# R212X.net
KiCad netlist of a schematic drawn in EAGLE
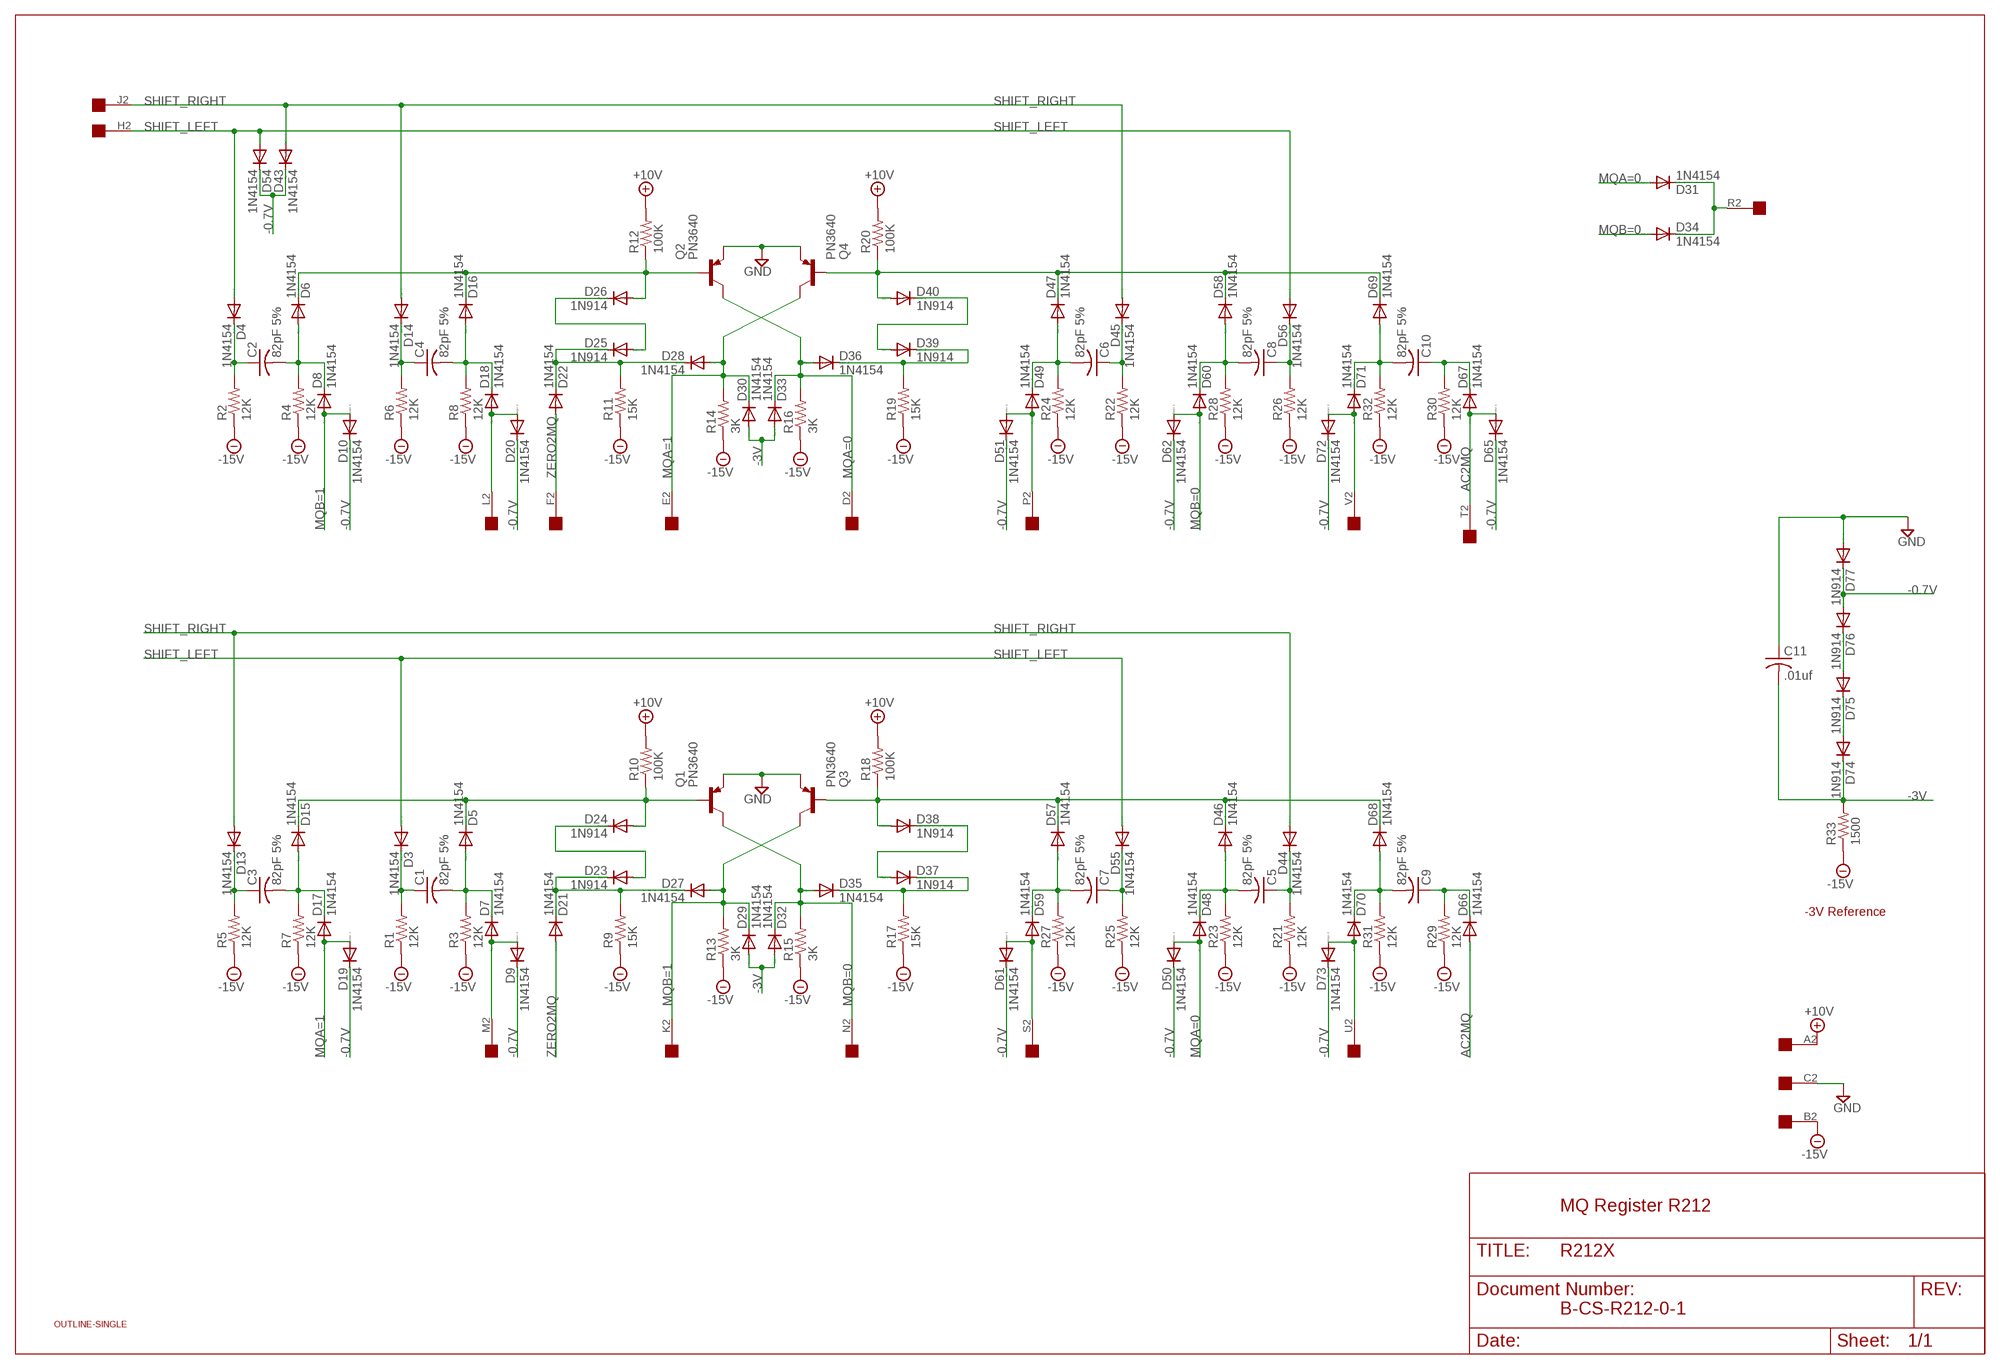
[diagram p0: schematic, sheet 1]

(export (version "E")
  (design (tool "Eeschema 10.0.6"))
  (components
    (comp (ref "C1")
      (value "82pF 5%")
      (footprint "eagle-import:C050-025X075")
      (libsource (lib "eagle-import") (part "C-US050-025X075"))
    )
    (comp (ref "C2")
      (value "82pF 5%")
      (footprint "eagle-import:C050-025X075")
      (libsource (lib "eagle-import") (part "C-US050-025X075"))
    )
    (comp (ref "C3")
      (value "82pF 5%")
      (footprint "eagle-import:C050-025X075")
      (libsource (lib "eagle-import") (part "C-US050-025X075"))
    )
    (comp (ref "C4")
      (value "82pF 5%")
      (footprint "eagle-import:C050-025X075")
      (libsource (lib "eagle-import") (part "C-US050-025X075"))
    )
    (comp (ref "C5")
      (value "82pF 5%")
      (footprint "eagle-import:C050-025X075")
      (libsource (lib "eagle-import") (part "C-US050-025X075"))
    )
    (comp (ref "C6")
      (value "82pF 5%")
      (footprint "eagle-import:C050-025X075")
      (libsource (lib "eagle-import") (part "C-US050-025X075"))
    )
    (comp (ref "C7")
      (value "82pF 5%")
      (footprint "eagle-import:C050-025X075")
      (libsource (lib "eagle-import") (part "C-US050-025X075"))
    )
    (comp (ref "C8")
      (value "82pF 5%")
      (footprint "eagle-import:C050-025X075")
      (libsource (lib "eagle-import") (part "C-US050-025X075"))
    )
    (comp (ref "C9")
      (value "82pF 5%")
      (footprint "eagle-import:C050-025X075")
      (libsource (lib "eagle-import") (part "C-US050-025X075"))
    )
    (comp (ref "C10")
      (value "82pF 5%")
      (footprint "eagle-import:C050-025X075")
      (libsource (lib "eagle-import") (part "C-US050-025X075"))
    )
    (comp (ref "C11")
      (value ".01uf")
      (footprint "eagle-import:C050-025X075")
      (libsource (lib "eagle-import") (part "C-US050-025X075"))
    )
    (comp (ref "D3")
      (value "1N4154")
      (footprint "eagle-import:DO35-10")
      (libsource (lib "eagle-import") (part "1N4148DO35-10"))
    )
    (comp (ref "D4")
      (value "1N4154")
      (footprint "eagle-import:DO35-10")
      (libsource (lib "eagle-import") (part "1N4148DO35-10"))
    )
    (comp (ref "D5")
      (value "1N4154")
      (footprint "eagle-import:DO35-10")
      (libsource (lib "eagle-import") (part "1N4148DO35-10"))
    )
    (comp (ref "D6")
      (value "1N4154")
      (footprint "eagle-import:DO35-10")
      (libsource (lib "eagle-import") (part "1N4148DO35-10"))
    )
    (comp (ref "D7")
      (value "1N4154")
      (footprint "eagle-import:DO35-10")
      (libsource (lib "eagle-import") (part "1N4148DO35-10"))
    )
    (comp (ref "D8")
      (value "1N4154")
      (footprint "eagle-import:DO35-10")
      (libsource (lib "eagle-import") (part "1N4148DO35-10"))
    )
    (comp (ref "D9")
      (value "1N4154")
      (footprint "eagle-import:DO35-10")
      (libsource (lib "eagle-import") (part "1N4148DO35-10"))
    )
    (comp (ref "D10")
      (value "1N4154")
      (footprint "eagle-import:DO35-10")
      (libsource (lib "eagle-import") (part "1N4148DO35-10"))
    )
    (comp (ref "D13")
      (value "1N4154")
      (footprint "eagle-import:DO35-10")
      (libsource (lib "eagle-import") (part "1N4148DO35-10"))
    )
    (comp (ref "D14")
      (value "1N4154")
      (footprint "eagle-import:DO35-10")
      (libsource (lib "eagle-import") (part "1N4148DO35-10"))
    )
    (comp (ref "D15")
      (value "1N4154")
      (footprint "eagle-import:DO35-10")
      (libsource (lib "eagle-import") (part "1N4148DO35-10"))
    )
    (comp (ref "D16")
      (value "1N4154")
      (footprint "eagle-import:DO35-10")
      (libsource (lib "eagle-import") (part "1N4148DO35-10"))
    )
    (comp (ref "D17")
      (value "1N4154")
      (footprint "eagle-import:DO35-10")
      (libsource (lib "eagle-import") (part "1N4148DO35-10"))
    )
    (comp (ref "D18")
      (value "1N4154")
      (footprint "eagle-import:DO35-10")
      (libsource (lib "eagle-import") (part "1N4148DO35-10"))
    )
    (comp (ref "D19")
      (value "1N4154")
      (footprint "eagle-import:DO35-10")
      (libsource (lib "eagle-import") (part "1N4148DO35-10"))
    )
    (comp (ref "D20")
      (value "1N4154")
      (footprint "eagle-import:DO35-10")
      (libsource (lib "eagle-import") (part "1N4148DO35-10"))
    )
    (comp (ref "D21")
      (value "1N4154")
      (footprint "eagle-import:DO35-10")
      (libsource (lib "eagle-import") (part "1N4148DO35-10"))
    )
    (comp (ref "D22")
      (value "1N4154")
      (footprint "eagle-import:DO35-10")
      (libsource (lib "eagle-import") (part "1N4148DO35-10"))
    )
    (comp (ref "D23")
      (value "1N914")
      (footprint "eagle-import:DO35-10")
      (libsource (lib "eagle-import") (part "1N4148DO35-10"))
    )
    (comp (ref "D24")
      (value "1N914")
      (footprint "eagle-import:DO35-10")
      (libsource (lib "eagle-import") (part "1N4148DO35-10"))
    )
    (comp (ref "D25")
      (value "1N914")
      (footprint "eagle-import:DO35-10")
      (libsource (lib "eagle-import") (part "1N4148DO35-10"))
    )
    (comp (ref "D26")
      (value "1N914")
      (footprint "eagle-import:DO35-10")
      (libsource (lib "eagle-import") (part "1N4148DO35-10"))
    )
    (comp (ref "D27")
      (value "1N4154")
      (footprint "eagle-import:DO35-10")
      (libsource (lib "eagle-import") (part "1N4148DO35-10"))
    )
    (comp (ref "D28")
      (value "1N4154")
      (footprint "eagle-import:DO35-10")
      (libsource (lib "eagle-import") (part "1N4148DO35-10"))
    )
    (comp (ref "D29")
      (value "1N4154")
      (footprint "eagle-import:DO35-10")
      (libsource (lib "eagle-import") (part "1N4148DO35-10"))
    )
    (comp (ref "D30")
      (value "1N4154")
      (footprint "eagle-import:DO35-10")
      (libsource (lib "eagle-import") (part "1N4148DO35-10"))
    )
    (comp (ref "D31")
      (value "1N4154")
      (footprint "eagle-import:DO35-10")
      (libsource (lib "eagle-import") (part "1N4148DO35-10"))
    )
    (comp (ref "D32")
      (value "1N4154")
      (footprint "eagle-import:DO35-10")
      (libsource (lib "eagle-import") (part "1N4148DO35-10"))
    )
    (comp (ref "D33")
      (value "1N4154")
      (footprint "eagle-import:DO35-10")
      (libsource (lib "eagle-import") (part "1N4148DO35-10"))
    )
    (comp (ref "D34")
      (value "1N4154")
      (footprint "eagle-import:DO35-10")
      (libsource (lib "eagle-import") (part "1N4148DO35-10"))
    )
    (comp (ref "D35")
      (value "1N4154")
      (footprint "eagle-import:DO35-10")
      (libsource (lib "eagle-import") (part "1N4148DO35-10"))
    )
    (comp (ref "D36")
      (value "1N4154")
      (footprint "eagle-import:DO35-10")
      (libsource (lib "eagle-import") (part "1N4148DO35-10"))
    )
    (comp (ref "D37")
      (value "1N914")
      (footprint "eagle-import:DO35-10")
      (libsource (lib "eagle-import") (part "1N4148DO35-10"))
    )
    (comp (ref "D38")
      (value "1N914")
      (footprint "eagle-import:DO35-10")
      (libsource (lib "eagle-import") (part "1N4148DO35-10"))
    )
    (comp (ref "D39")
      (value "1N914")
      (footprint "eagle-import:DO35-10")
      (libsource (lib "eagle-import") (part "1N4148DO35-10"))
    )
    (comp (ref "D40")
      (value "1N914")
      (footprint "eagle-import:DO35-10")
      (libsource (lib "eagle-import") (part "1N4148DO35-10"))
    )
    (comp (ref "D43")
      (value "1N4154")
      (footprint "eagle-import:DO35-10")
      (libsource (lib "eagle-import") (part "1N4148DO35-10"))
    )
    (comp (ref "D44")
      (value "1N4154")
      (footprint "eagle-import:DO35-10")
      (libsource (lib "eagle-import") (part "1N4148DO35-10"))
    )
    (comp (ref "D45")
      (value "1N4154")
      (footprint "eagle-import:DO35-10")
      (libsource (lib "eagle-import") (part "1N4148DO35-10"))
    )
    (comp (ref "D46")
      (value "1N4154")
      (footprint "eagle-import:DO35-10")
      (libsource (lib "eagle-import") (part "1N4148DO35-10"))
    )
    (comp (ref "D47")
      (value "1N4154")
      (footprint "eagle-import:DO35-10")
      (libsource (lib "eagle-import") (part "1N4148DO35-10"))
    )
    (comp (ref "D48")
      (value "1N4154")
      (footprint "eagle-import:DO35-10")
      (libsource (lib "eagle-import") (part "1N4148DO35-10"))
    )
    (comp (ref "D49")
      (value "1N4154")
      (footprint "eagle-import:DO35-10")
      (libsource (lib "eagle-import") (part "1N4148DO35-10"))
    )
    (comp (ref "D50")
      (value "1N4154")
      (footprint "eagle-import:DO35-10")
      (libsource (lib "eagle-import") (part "1N4148DO35-10"))
    )
    (comp (ref "D51")
      (value "1N4154")
      (footprint "eagle-import:DO35-10")
      (libsource (lib "eagle-import") (part "1N4148DO35-10"))
    )
    (comp (ref "D54")
      (value "1N4154")
      (footprint "eagle-import:DO35-10")
      (libsource (lib "eagle-import") (part "1N4148DO35-10"))
    )
    (comp (ref "D55")
      (value "1N4154")
      (footprint "eagle-import:DO35-10")
      (libsource (lib "eagle-import") (part "1N4148DO35-10"))
    )
    (comp (ref "D56")
      (value "1N4154")
      (footprint "eagle-import:DO35-10")
      (libsource (lib "eagle-import") (part "1N4148DO35-10"))
    )
    (comp (ref "D57")
      (value "1N4154")
      (footprint "eagle-import:DO35-10")
      (libsource (lib "eagle-import") (part "1N4148DO35-10"))
    )
    (comp (ref "D58")
      (value "1N4154")
      (footprint "eagle-import:DO35-10")
      (libsource (lib "eagle-import") (part "1N4148DO35-10"))
    )
    (comp (ref "D59")
      (value "1N4154")
      (footprint "eagle-import:DO35-10")
      (libsource (lib "eagle-import") (part "1N4148DO35-10"))
    )
    (comp (ref "D60")
      (value "1N4154")
      (footprint "eagle-import:DO35-10")
      (libsource (lib "eagle-import") (part "1N4148DO35-10"))
    )
    (comp (ref "D61")
      (value "1N4154")
      (footprint "eagle-import:DO35-10")
      (libsource (lib "eagle-import") (part "1N4148DO35-10"))
    )
    (comp (ref "D62")
      (value "1N4154")
      (footprint "eagle-import:DO35-10")
      (libsource (lib "eagle-import") (part "1N4148DO35-10"))
    )
    (comp (ref "D65")
      (value "1N4154")
      (footprint "eagle-import:DO35-10")
      (libsource (lib "eagle-import") (part "1N4148DO35-10"))
    )
    (comp (ref "D66")
      (value "1N4154")
      (footprint "eagle-import:DO35-10")
      (libsource (lib "eagle-import") (part "1N4148DO35-10"))
    )
    (comp (ref "D67")
      (value "1N4154")
      (footprint "eagle-import:DO35-10")
      (libsource (lib "eagle-import") (part "1N4148DO35-10"))
    )
    (comp (ref "D68")
      (value "1N4154")
      (footprint "eagle-import:DO35-10")
      (libsource (lib "eagle-import") (part "1N4148DO35-10"))
    )
    (comp (ref "D69")
      (value "1N4154")
      (footprint "eagle-import:DO35-10")
      (libsource (lib "eagle-import") (part "1N4148DO35-10"))
    )
    (comp (ref "D70")
      (value "1N4154")
      (footprint "eagle-import:DO35-10")
      (libsource (lib "eagle-import") (part "1N4148DO35-10"))
    )
    (comp (ref "D71")
      (value "1N4154")
      (footprint "eagle-import:DO35-10")
      (libsource (lib "eagle-import") (part "1N4148DO35-10"))
    )
    (comp (ref "D72")
      (value "1N4154")
      (footprint "eagle-import:DO35-10")
      (libsource (lib "eagle-import") (part "1N4148DO35-10"))
    )
    (comp (ref "D73")
      (value "1N4154")
      (footprint "eagle-import:DO35-10")
      (libsource (lib "eagle-import") (part "1N4148DO35-10"))
    )
    (comp (ref "D74")
      (value "1N914")
      (footprint "eagle-import:DO35-10")
      (libsource (lib "eagle-import") (part "1N4148DO35-10"))
    )
    (comp (ref "D75")
      (value "1N914")
      (footprint "eagle-import:DO35-10")
      (libsource (lib "eagle-import") (part "1N4148DO35-10"))
    )
    (comp (ref "D76")
      (value "1N914")
      (footprint "eagle-import:DO35-10")
      (libsource (lib "eagle-import") (part "1N4148DO35-10"))
    )
    (comp (ref "D77")
      (value "1N914")
      (footprint "eagle-import:DO35-10")
      (libsource (lib "eagle-import") (part "1N4148DO35-10"))
    )
    (comp (ref "Q1")
      (value "PN3640")
      (footprint "eagle-import:TO39")
      (libsource (lib "eagle-import") (part "2N3637"))
    )
    (comp (ref "Q2")
      (value "PN3640")
      (footprint "eagle-import:TO39")
      (libsource (lib "eagle-import") (part "2N3637"))
    )
    (comp (ref "Q3")
      (value "PN3640")
      (footprint "eagle-import:TO39")
      (libsource (lib "eagle-import") (part "2N3637"))
    )
    (comp (ref "Q4")
      (value "PN3640")
      (footprint "eagle-import:TO39")
      (libsource (lib "eagle-import") (part "2N3637"))
    )
    (comp (ref "R1")
      (value "12K")
      (footprint "eagle-import:0207_10")
      (libsource (lib "eagle-import") (part "R-US_0207/10"))
    )
    (comp (ref "R2")
      (value "12K")
      (footprint "eagle-import:0207_10")
      (libsource (lib "eagle-import") (part "R-US_0207/10"))
    )
    (comp (ref "R3")
      (value "12K")
      (footprint "eagle-import:0207_10")
      (libsource (lib "eagle-import") (part "R-US_0207/10"))
    )
    (comp (ref "R4")
      (value "12K")
      (footprint "eagle-import:0207_10")
      (libsource (lib "eagle-import") (part "R-US_0207/10"))
    )
    (comp (ref "R5")
      (value "12K")
      (footprint "eagle-import:0207_10")
      (libsource (lib "eagle-import") (part "R-US_0207/10"))
    )
    (comp (ref "R6")
      (value "12K")
      (footprint "eagle-import:0207_10")
      (libsource (lib "eagle-import") (part "R-US_0207/10"))
    )
    (comp (ref "R7")
      (value "12K")
      (footprint "eagle-import:0207_10")
      (libsource (lib "eagle-import") (part "R-US_0207/10"))
    )
    (comp (ref "R8")
      (value "12K")
      (footprint "eagle-import:0207_10")
      (libsource (lib "eagle-import") (part "R-US_0207/10"))
    )
    (comp (ref "R9")
      (value "15K")
      (footprint "eagle-import:0207_10")
      (libsource (lib "eagle-import") (part "R-US_0207/10"))
    )
    (comp (ref "R10")
      (value "100K")
      (footprint "eagle-import:0207_10")
      (libsource (lib "eagle-import") (part "R-US_0207/10"))
    )
    (comp (ref "R11")
      (value "15K")
      (footprint "eagle-import:0207_10")
      (libsource (lib "eagle-import") (part "R-US_0207/10"))
    )
    (comp (ref "R12")
      (value "100K")
      (footprint "eagle-import:0207_10")
      (libsource (lib "eagle-import") (part "R-US_0207/10"))
    )
    (comp (ref "R13")
      (value "3K")
      (footprint "eagle-import:0207_10")
      (libsource (lib "eagle-import") (part "R-US_0207/10"))
    )
    (comp (ref "R14")
      (value "3K")
      (footprint "eagle-import:0207_10")
      (libsource (lib "eagle-import") (part "R-US_0207/10"))
    )
    (comp (ref "R15")
      (value "3K")
      (footprint "eagle-import:0207_10")
      (libsource (lib "eagle-import") (part "R-US_0207/10"))
    )
    (comp (ref "R16")
      (value "3K")
      (footprint "eagle-import:0207_10")
      (libsource (lib "eagle-import") (part "R-US_0207/10"))
    )
    (comp (ref "R17")
      (value "15K")
      (footprint "eagle-import:0207_10")
      (libsource (lib "eagle-import") (part "R-US_0207/10"))
    )
    (comp (ref "R18")
      (value "100K")
      (footprint "eagle-import:0207_10")
      (libsource (lib "eagle-import") (part "R-US_0207/10"))
    )
    (comp (ref "R19")
      (value "15K")
      (footprint "eagle-import:0207_10")
      (libsource (lib "eagle-import") (part "R-US_0207/10"))
    )
    (comp (ref "R20")
      (value "100K")
      (footprint "eagle-import:0207_10")
      (libsource (lib "eagle-import") (part "R-US_0207/10"))
    )
    (comp (ref "R21")
      (value "12K")
      (footprint "eagle-import:0207_10")
      (libsource (lib "eagle-import") (part "R-US_0207/10"))
    )
    (comp (ref "R22")
      (value "12K")
      (footprint "eagle-import:0207_10")
      (libsource (lib "eagle-import") (part "R-US_0207/10"))
    )
    (comp (ref "R23")
      (value "12K")
      (footprint "eagle-import:0207_10")
      (libsource (lib "eagle-import") (part "R-US_0207/10"))
    )
    (comp (ref "R24")
      (value "12K")
      (footprint "eagle-import:0207_10")
      (libsource (lib "eagle-import") (part "R-US_0207/10"))
    )
    (comp (ref "R25")
      (value "12K")
      (footprint "eagle-import:0207_10")
      (libsource (lib "eagle-import") (part "R-US_0207/10"))
    )
    (comp (ref "R26")
      (value "12K")
      (footprint "eagle-import:0207_10")
      (libsource (lib "eagle-import") (part "R-US_0207/10"))
    )
    (comp (ref "R27")
      (value "12K")
      (footprint "eagle-import:0207_10")
      (libsource (lib "eagle-import") (part "R-US_0207/10"))
    )
    (comp (ref "R28")
      (value "12K")
      (footprint "eagle-import:0207_10")
      (libsource (lib "eagle-import") (part "R-US_0207/10"))
    )
    (comp (ref "R29")
      (value "12K")
      (footprint "eagle-import:0207_10")
      (libsource (lib "eagle-import") (part "R-US_0207/10"))
    )
    (comp (ref "R30")
      (value "12K")
      (footprint "eagle-import:0207_10")
      (libsource (lib "eagle-import") (part "R-US_0207/10"))
    )
    (comp (ref "R31")
      (value "12K")
      (footprint "eagle-import:0207_10")
      (libsource (lib "eagle-import") (part "R-US_0207/10"))
    )
    (comp (ref "R32")
      (value "12K")
      (footprint "eagle-import:0207_10")
      (libsource (lib "eagle-import") (part "R-US_0207/10"))
    )
    (comp (ref "R33")
      (value "1500")
      (footprint "eagle-import:0207_10")
      (libsource (lib "eagle-import") (part "R-US_0207/10"))
    )
    (comp (ref "U$1")
      (value "OUTLINE-SINGLE")
      (footprint "eagle-import:SINGLE")
      (libsource (lib "eagle-import") (part "OUTLINE-SINGLE"))
    )
    (comp (ref "U$2")
      (value "EDGE-1")
      (footprint "eagle-import:EDGE-CON1")
      (libsource (lib "eagle-import") (part "EDGE-1"))
    )
  )
  (nets
    (net (code "1") (name "+10V") (class "Default")
      (node (ref "R10") (pin "2") (pinfunction "2_2") (pintype "passive"))
      (node (ref "R12") (pin "2") (pinfunction "2_2") (pintype "passive"))
      (node (ref "R18") (pin "2") (pinfunction "2_2") (pintype "passive"))
      (node (ref "R20") (pin "2") (pinfunction "2_2") (pintype "passive"))
      (node (ref "U$2") (pin "A2") (pinfunction "1_A2") (pintype "bidirectional"))
    )
    (net (code "2") (name "-15V") (class "Default")
      (node (ref "R1") (pin "1") (pinfunction "1_1") (pintype "passive"))
      (node (ref "R11") (pin "1") (pinfunction "1_1") (pintype "passive"))
      (node (ref "R13") (pin "1") (pinfunction "1_1") (pintype "passive"))
      (node (ref "R14") (pin "1") (pinfunction "1_1") (pintype "passive"))
      (node (ref "R15") (pin "1") (pinfunction "1_1") (pintype "passive"))
      (node (ref "R16") (pin "1") (pinfunction "1_1") (pintype "passive"))
      (node (ref "R17") (pin "1") (pinfunction "1_1") (pintype "passive"))
      (node (ref "R19") (pin "1") (pinfunction "1_1") (pintype "passive"))
      (node (ref "R2") (pin "1") (pinfunction "1_1") (pintype "passive"))
      (node (ref "R21") (pin "1") (pinfunction "1_1") (pintype "passive"))
      (node (ref "R22") (pin "1") (pinfunction "1_1") (pintype "passive"))
      (node (ref "R23") (pin "1") (pinfunction "1_1") (pintype "passive"))
      (node (ref "R24") (pin "1") (pinfunction "1_1") (pintype "passive"))
      (node (ref "R25") (pin "1") (pinfunction "1_1") (pintype "passive"))
      (node (ref "R26") (pin "1") (pinfunction "1_1") (pintype "passive"))
      (node (ref "R27") (pin "1") (pinfunction "1_1") (pintype "passive"))
      (node (ref "R28") (pin "1") (pinfunction "1_1") (pintype "passive"))
      (node (ref "R29") (pin "1") (pinfunction "1_1") (pintype "passive"))
      (node (ref "R3") (pin "1") (pinfunction "1_1") (pintype "passive"))
      (node (ref "R30") (pin "1") (pinfunction "1_1") (pintype "passive"))
      (node (ref "R31") (pin "1") (pinfunction "1_1") (pintype "passive"))
      (node (ref "R32") (pin "1") (pinfunction "1_1") (pintype "passive"))
      (node (ref "R33") (pin "1") (pinfunction "1_1") (pintype "passive"))
      (node (ref "R4") (pin "1") (pinfunction "1_1") (pintype "passive"))
      (node (ref "R5") (pin "1") (pinfunction "1_1") (pintype "passive"))
      (node (ref "R6") (pin "1") (pinfunction "1_1") (pintype "passive"))
      (node (ref "R7") (pin "1") (pinfunction "1_1") (pintype "passive"))
      (node (ref "R8") (pin "1") (pinfunction "1_1") (pintype "passive"))
      (node (ref "R9") (pin "1") (pinfunction "1_1") (pintype "passive"))
      (node (ref "U$2") (pin "B2") (pinfunction "1_B2") (pintype "bidirectional"))
    )
    (net (code "3") (name "/-0.7V") (class "Default")
      (node (ref "D10") (pin "C") (pinfunction "C_C") (pintype "passive"))
      (node (ref "D19") (pin "C") (pinfunction "C_C") (pintype "passive"))
      (node (ref "D20") (pin "C") (pinfunction "C_C") (pintype "passive"))
      (node (ref "D43") (pin "C") (pinfunction "C_C") (pintype "passive"))
      (node (ref "D50") (pin "C") (pinfunction "C_C") (pintype "passive"))
      (node (ref "D51") (pin "C") (pinfunction "C_C") (pintype "passive"))
      (node (ref "D54") (pin "C") (pinfunction "C_C") (pintype "passive"))
      (node (ref "D61") (pin "C") (pinfunction "C_C") (pintype "passive"))
      (node (ref "D62") (pin "C") (pinfunction "C_C") (pintype "passive"))
      (node (ref "D65") (pin "C") (pinfunction "C_C") (pintype "passive"))
      (node (ref "D72") (pin "C") (pinfunction "C_C") (pintype "passive"))
      (node (ref "D73") (pin "C") (pinfunction "C_C") (pintype "passive"))
      (node (ref "D76") (pin "A") (pinfunction "A_A") (pintype "passive"))
      (node (ref "D77") (pin "C") (pinfunction "C_C") (pintype "passive"))
      (node (ref "D9") (pin "C") (pinfunction "C_C") (pintype "passive"))
    )
    (net (code "4") (name "/-3V") (class "Default")
      (node (ref "C11") (pin "2") (pinfunction "2_2") (pintype "passive"))
      (node (ref "D29") (pin "A") (pinfunction "A_A") (pintype "passive"))
      (node (ref "D30") (pin "A") (pinfunction "A_A") (pintype "passive"))
      (node (ref "D32") (pin "A") (pinfunction "A_A") (pintype "passive"))
      (node (ref "D33") (pin "A") (pinfunction "A_A") (pintype "passive"))
      (node (ref "D74") (pin "C") (pinfunction "C_C") (pintype "passive"))
      (node (ref "R33") (pin "2") (pinfunction "2_2") (pintype "passive"))
    )
    (net (code "5") (name "/AC2MQ") (class "Default")
      (node (ref "D65") (pin "A") (pinfunction "A_A") (pintype "passive"))
      (node (ref "D66") (pin "A") (pinfunction "A_A") (pintype "passive"))
      (node (ref "D67") (pin "A") (pinfunction "A_A") (pintype "passive"))
      (node (ref "U$2") (pin "T2") (pinfunction "1_T2") (pintype "bidirectional"))
    )
    (net (code "6") (name "/MQA=0") (class "Default")
      (node (ref "D31") (pin "A") (pinfunction "A_A") (pintype "passive"))
      (node (ref "D33") (pin "C") (pinfunction "C_C") (pintype "passive"))
      (node (ref "D36") (pin "A") (pinfunction "A_A") (pintype "passive"))
      (node (ref "D48") (pin "A") (pinfunction "A_A") (pintype "passive"))
      (node (ref "D50") (pin "A") (pinfunction "A_A") (pintype "passive"))
      (node (ref "Q2") (pin "3") (pinfunction "C_3") (pintype "passive"))
      (node (ref "R16") (pin "2") (pinfunction "2_2") (pintype "passive"))
      (node (ref "U$2") (pin "D2") (pinfunction "1_D2") (pintype "bidirectional"))
    )
    (net (code "7") (name "/MQA=1") (class "Default")
      (node (ref "D17") (pin "A") (pinfunction "A_A") (pintype "passive"))
      (node (ref "D19") (pin "A") (pinfunction "A_A") (pintype "passive"))
      (node (ref "D28") (pin "A") (pinfunction "A_A") (pintype "passive"))
      (node (ref "D30") (pin "C") (pinfunction "C_C") (pintype "passive"))
      (node (ref "Q4") (pin "3") (pinfunction "C_3") (pintype "passive"))
      (node (ref "R14") (pin "2") (pinfunction "2_2") (pintype "passive"))
      (node (ref "U$2") (pin "E2") (pinfunction "1_E2") (pintype "bidirectional"))
    )
    (net (code "8") (name "/MQB=0") (class "Default")
      (node (ref "D32") (pin "C") (pinfunction "C_C") (pintype "passive"))
      (node (ref "D34") (pin "A") (pinfunction "A_A") (pintype "passive"))
      (node (ref "D35") (pin "A") (pinfunction "A_A") (pintype "passive"))
      (node (ref "D60") (pin "A") (pinfunction "A_A") (pintype "passive"))
      (node (ref "D62") (pin "A") (pinfunction "A_A") (pintype "passive"))
      (node (ref "Q1") (pin "3") (pinfunction "C_3") (pintype "passive"))
      (node (ref "R15") (pin "2") (pinfunction "2_2") (pintype "passive"))
      (node (ref "U$2") (pin "N2") (pinfunction "1_N2") (pintype "bidirectional"))
    )
    (net (code "9") (name "/MQB=1") (class "Default")
      (node (ref "D10") (pin "A") (pinfunction "A_A") (pintype "passive"))
      (node (ref "D27") (pin "A") (pinfunction "A_A") (pintype "passive"))
      (node (ref "D29") (pin "C") (pinfunction "C_C") (pintype "passive"))
      (node (ref "D8") (pin "A") (pinfunction "A_A") (pintype "passive"))
      (node (ref "Q3") (pin "3") (pinfunction "C_3") (pintype "passive"))
      (node (ref "R13") (pin "2") (pinfunction "2_2") (pintype "passive"))
      (node (ref "U$2") (pin "K2") (pinfunction "1_K2") (pintype "bidirectional"))
    )
    (net (code "10") (name "/SHIFT_LEFT") (class "Default")
      (node (ref "D3") (pin "A") (pinfunction "A_A") (pintype "passive"))
      (node (ref "D4") (pin "A") (pinfunction "A_A") (pintype "passive"))
      (node (ref "D54") (pin "A") (pinfunction "A_A") (pintype "passive"))
      (node (ref "D55") (pin "A") (pinfunction "A_A") (pintype "passive"))
      (node (ref "D56") (pin "A") (pinfunction "A_A") (pintype "passive"))
      (node (ref "U$2") (pin "H2") (pinfunction "1_H2") (pintype "bidirectional"))
    )
    (net (code "11") (name "/SHIFT_RIGHT") (class "Default")
      (node (ref "D13") (pin "A") (pinfunction "A_A") (pintype "passive"))
      (node (ref "D14") (pin "A") (pinfunction "A_A") (pintype "passive"))
      (node (ref "D43") (pin "A") (pinfunction "A_A") (pintype "passive"))
      (node (ref "D44") (pin "A") (pinfunction "A_A") (pintype "passive"))
      (node (ref "D45") (pin "A") (pinfunction "A_A") (pintype "passive"))
      (node (ref "U$2") (pin "J2") (pinfunction "1_J2") (pintype "bidirectional"))
    )
    (net (code "12") (name "/ZERO2MQ") (class "Default")
      (node (ref "D21") (pin "A") (pinfunction "A_A") (pintype "passive"))
      (node (ref "D22") (pin "A") (pinfunction "A_A") (pintype "passive"))
      (node (ref "U$2") (pin "F2") (pinfunction "1_F2") (pintype "bidirectional"))
    )
    (net (code "13") (name "GND") (class "Default")
      (node (ref "C11") (pin "1") (pinfunction "1_1") (pintype "passive"))
      (node (ref "D77") (pin "A") (pinfunction "A_A") (pintype "passive"))
      (node (ref "Q1") (pin "1") (pinfunction "E_1") (pintype "passive"))
      (node (ref "Q2") (pin "1") (pinfunction "E_1") (pintype "passive"))
      (node (ref "Q3") (pin "1") (pinfunction "E_1") (pintype "passive"))
      (node (ref "Q4") (pin "1") (pinfunction "E_1") (pintype "passive"))
      (node (ref "U$2") (pin "C2") (pinfunction "1_C2") (pintype "bidirectional"))
    )
    (net (code "14") (name "Net-(C1-Pad1)") (class "Default")
      (node (ref "C1") (pin "1") (pinfunction "1_1") (pintype "passive"))
      (node (ref "D3") (pin "C") (pinfunction "C_C") (pintype "passive"))
      (node (ref "R1") (pin "2") (pinfunction "2_2") (pintype "passive"))
    )
    (net (code "15") (name "Net-(C1-Pad2)") (class "Default")
      (node (ref "C1") (pin "2") (pinfunction "2_2") (pintype "passive"))
      (node (ref "D5") (pin "A") (pinfunction "A_A") (pintype "passive"))
      (node (ref "D7") (pin "C") (pinfunction "C_C") (pintype "passive"))
      (node (ref "R3") (pin "2") (pinfunction "2_2") (pintype "passive"))
    )
    (net (code "16") (name "Net-(C2-Pad1)") (class "Default")
      (node (ref "C2") (pin "1") (pinfunction "1_1") (pintype "passive"))
      (node (ref "D4") (pin "C") (pinfunction "C_C") (pintype "passive"))
      (node (ref "R2") (pin "2") (pinfunction "2_2") (pintype "passive"))
    )
    (net (code "17") (name "Net-(C2-Pad2)") (class "Default")
      (node (ref "C2") (pin "2") (pinfunction "2_2") (pintype "passive"))
      (node (ref "D6") (pin "A") (pinfunction "A_A") (pintype "passive"))
      (node (ref "D8") (pin "C") (pinfunction "C_C") (pintype "passive"))
      (node (ref "R4") (pin "2") (pinfunction "2_2") (pintype "passive"))
    )
    (net (code "18") (name "Net-(C3-Pad1)") (class "Default")
      (node (ref "C3") (pin "1") (pinfunction "1_1") (pintype "passive"))
      (node (ref "D13") (pin "C") (pinfunction "C_C") (pintype "passive"))
      (node (ref "R5") (pin "2") (pinfunction "2_2") (pintype "passive"))
    )
    (net (code "19") (name "Net-(C3-Pad2)") (class "Default")
      (node (ref "C3") (pin "2") (pinfunction "2_2") (pintype "passive"))
      (node (ref "D15") (pin "A") (pinfunction "A_A") (pintype "passive"))
      (node (ref "D17") (pin "C") (pinfunction "C_C") (pintype "passive"))
      (node (ref "R7") (pin "2") (pinfunction "2_2") (pintype "passive"))
    )
    (net (code "20") (name "Net-(C4-Pad1)") (class "Default")
      (node (ref "C4") (pin "1") (pinfunction "1_1") (pintype "passive"))
      (node (ref "D14") (pin "C") (pinfunction "C_C") (pintype "passive"))
      (node (ref "R6") (pin "2") (pinfunction "2_2") (pintype "passive"))
    )
    (net (code "21") (name "Net-(C4-Pad2)") (class "Default")
      (node (ref "C4") (pin "2") (pinfunction "2_2") (pintype "passive"))
      (node (ref "D16") (pin "A") (pinfunction "A_A") (pintype "passive"))
      (node (ref "D18") (pin "C") (pinfunction "C_C") (pintype "passive"))
      (node (ref "R8") (pin "2") (pinfunction "2_2") (pintype "passive"))
    )
    (net (code "22") (name "Net-(C5-Pad1)") (class "Default")
      (node (ref "C5") (pin "1") (pinfunction "1_1") (pintype "passive"))
      (node (ref "D44") (pin "C") (pinfunction "C_C") (pintype "passive"))
      (node (ref "R21") (pin "2") (pinfunction "2_2") (pintype "passive"))
    )
    (net (code "23") (name "Net-(C5-Pad2)") (class "Default")
      (node (ref "C5") (pin "2") (pinfunction "2_2") (pintype "passive"))
      (node (ref "D46") (pin "A") (pinfunction "A_A") (pintype "passive"))
      (node (ref "D48") (pin "C") (pinfunction "C_C") (pintype "passive"))
      (node (ref "R23") (pin "2") (pinfunction "2_2") (pintype "passive"))
    )
    (net (code "24") (name "Net-(C6-Pad1)") (class "Default")
      (node (ref "C6") (pin "1") (pinfunction "1_1") (pintype "passive"))
      (node (ref "D45") (pin "C") (pinfunction "C_C") (pintype "passive"))
      (node (ref "R22") (pin "2") (pinfunction "2_2") (pintype "passive"))
    )
    (net (code "25") (name "Net-(C6-Pad2)") (class "Default")
      (node (ref "C6") (pin "2") (pinfunction "2_2") (pintype "passive"))
      (node (ref "D47") (pin "A") (pinfunction "A_A") (pintype "passive"))
      (node (ref "D49") (pin "C") (pinfunction "C_C") (pintype "passive"))
      (node (ref "R24") (pin "2") (pinfunction "2_2") (pintype "passive"))
    )
    (net (code "26") (name "Net-(C7-Pad1)") (class "Default")
      (node (ref "C7") (pin "1") (pinfunction "1_1") (pintype "passive"))
      (node (ref "D55") (pin "C") (pinfunction "C_C") (pintype "passive"))
      (node (ref "R25") (pin "2") (pinfunction "2_2") (pintype "passive"))
    )
    (net (code "27") (name "Net-(C7-Pad2)") (class "Default")
      (node (ref "C7") (pin "2") (pinfunction "2_2") (pintype "passive"))
      (node (ref "D57") (pin "A") (pinfunction "A_A") (pintype "passive"))
      (node (ref "D59") (pin "C") (pinfunction "C_C") (pintype "passive"))
      (node (ref "R27") (pin "2") (pinfunction "2_2") (pintype "passive"))
    )
    (net (code "28") (name "Net-(C8-Pad1)") (class "Default")
      (node (ref "C8") (pin "1") (pinfunction "1_1") (pintype "passive"))
      (node (ref "D56") (pin "C") (pinfunction "C_C") (pintype "passive"))
      (node (ref "R26") (pin "2") (pinfunction "2_2") (pintype "passive"))
    )
    (net (code "29") (name "Net-(C8-Pad2)") (class "Default")
      (node (ref "C8") (pin "2") (pinfunction "2_2") (pintype "passive"))
      (node (ref "D58") (pin "A") (pinfunction "A_A") (pintype "passive"))
      (node (ref "D60") (pin "C") (pinfunction "C_C") (pintype "passive"))
      (node (ref "R28") (pin "2") (pinfunction "2_2") (pintype "passive"))
    )
    (net (code "30") (name "Net-(C9-Pad1)") (class "Default")
      (node (ref "C9") (pin "1") (pinfunction "1_1") (pintype "passive"))
      (node (ref "D66") (pin "C") (pinfunction "C_C") (pintype "passive"))
      (node (ref "R29") (pin "2") (pinfunction "2_2") (pintype "passive"))
    )
    (net (code "31") (name "Net-(C9-Pad2)") (class "Default")
      (node (ref "C9") (pin "2") (pinfunction "2_2") (pintype "passive"))
      (node (ref "D68") (pin "A") (pinfunction "A_A") (pintype "passive"))
      (node (ref "D70") (pin "C") (pinfunction "C_C") (pintype "passive"))
      (node (ref "R31") (pin "2") (pinfunction "2_2") (pintype "passive"))
    )
    (net (code "32") (name "Net-(C10-Pad1)") (class "Default")
      (node (ref "C10") (pin "1") (pinfunction "1_1") (pintype "passive"))
      (node (ref "D67") (pin "C") (pinfunction "C_C") (pintype "passive"))
      (node (ref "R30") (pin "2") (pinfunction "2_2") (pintype "passive"))
    )
    (net (code "33") (name "Net-(C10-Pad2)") (class "Default")
      (node (ref "C10") (pin "2") (pinfunction "2_2") (pintype "passive"))
      (node (ref "D69") (pin "A") (pinfunction "A_A") (pintype "passive"))
      (node (ref "D71") (pin "C") (pinfunction "C_C") (pintype "passive"))
      (node (ref "R32") (pin "2") (pinfunction "2_2") (pintype "passive"))
    )
    (net (code "34") (name "Net-(D21-PadC)") (class "Default")
      (node (ref "D21") (pin "C") (pinfunction "C_C") (pintype "passive"))
      (node (ref "D23") (pin "C") (pinfunction "C_C") (pintype "passive"))
      (node (ref "D27") (pin "C") (pinfunction "C_C") (pintype "passive"))
      (node (ref "R9") (pin "2") (pinfunction "2_2") (pintype "passive"))
    )
    (net (code "35") (name "Net-(D22-PadC)") (class "Default")
      (node (ref "D22") (pin "C") (pinfunction "C_C") (pintype "passive"))
      (node (ref "D25") (pin "C") (pinfunction "C_C") (pintype "passive"))
      (node (ref "D28") (pin "C") (pinfunction "C_C") (pintype "passive"))
      (node (ref "R11") (pin "2") (pinfunction "2_2") (pintype "passive"))
    )
    (net (code "36") (name "Net-(D23-PadA)") (class "Default")
      (node (ref "D23") (pin "A") (pinfunction "A_A") (pintype "passive"))
      (node (ref "D24") (pin "C") (pinfunction "C_C") (pintype "passive"))
    )
    (net (code "37") (name "Net-(D25-PadA)") (class "Default")
      (node (ref "D25") (pin "A") (pinfunction "A_A") (pintype "passive"))
      (node (ref "D26") (pin "C") (pinfunction "C_C") (pintype "passive"))
    )
    (net (code "38") (name "Net-(D35-PadC)") (class "Default")
      (node (ref "D35") (pin "C") (pinfunction "C_C") (pintype "passive"))
      (node (ref "D37") (pin "C") (pinfunction "C_C") (pintype "passive"))
      (node (ref "R17") (pin "2") (pinfunction "2_2") (pintype "passive"))
    )
    (net (code "39") (name "Net-(D36-PadC)") (class "Default")
      (node (ref "D36") (pin "C") (pinfunction "C_C") (pintype "passive"))
      (node (ref "D39") (pin "C") (pinfunction "C_C") (pintype "passive"))
      (node (ref "R19") (pin "2") (pinfunction "2_2") (pintype "passive"))
    )
    (net (code "40") (name "Net-(D37-PadA)") (class "Default")
      (node (ref "D37") (pin "A") (pinfunction "A_A") (pintype "passive"))
      (node (ref "D38") (pin "C") (pinfunction "C_C") (pintype "passive"))
    )
    (net (code "41") (name "Net-(D39-PadA)") (class "Default")
      (node (ref "D39") (pin "A") (pinfunction "A_A") (pintype "passive"))
      (node (ref "D40") (pin "C") (pinfunction "C_C") (pintype "passive"))
    )
    (net (code "42") (name "Net-(D74-PadA)") (class "Default")
      (node (ref "D74") (pin "A") (pinfunction "A_A") (pintype "passive"))
      (node (ref "D75") (pin "C") (pinfunction "C_C") (pintype "passive"))
    )
    (net (code "43") (name "Net-(D75-PadA)") (class "Default")
      (node (ref "D75") (pin "A") (pinfunction "A_A") (pintype "passive"))
      (node (ref "D76") (pin "C") (pinfunction "C_C") (pintype "passive"))
    )
    (net (code "44") (name "Net-(Q1-B)") (class "Default")
      (node (ref "D15") (pin "C") (pinfunction "C_C") (pintype "passive"))
      (node (ref "D24") (pin "A") (pinfunction "A_A") (pintype "passive"))
      (node (ref "D5") (pin "C") (pinfunction "C_C") (pintype "passive"))
      (node (ref "Q1") (pin "2") (pinfunction "B_2") (pintype "passive"))
      (node (ref "R10") (pin "1") (pinfunction "1_1") (pintype "passive"))
    )
    (net (code "45") (name "Net-(Q2-B)") (class "Default")
      (node (ref "D16") (pin "C") (pinfunction "C_C") (pintype "passive"))
      (node (ref "D26") (pin "A") (pinfunction "A_A") (pintype "passive"))
      (node (ref "D6") (pin "C") (pinfunction "C_C") (pintype "passive"))
      (node (ref "Q2") (pin "2") (pinfunction "B_2") (pintype "passive"))
      (node (ref "R12") (pin "1") (pinfunction "1_1") (pintype "passive"))
    )
    (net (code "46") (name "Net-(Q3-B)") (class "Default")
      (node (ref "D38") (pin "A") (pinfunction "A_A") (pintype "passive"))
      (node (ref "D46") (pin "C") (pinfunction "C_C") (pintype "passive"))
      (node (ref "D57") (pin "C") (pinfunction "C_C") (pintype "passive"))
      (node (ref "D68") (pin "C") (pinfunction "C_C") (pintype "passive"))
      (node (ref "Q3") (pin "2") (pinfunction "B_2") (pintype "passive"))
      (node (ref "R18") (pin "1") (pinfunction "1_1") (pintype "passive"))
    )
    (net (code "47") (name "Net-(Q4-B)") (class "Default")
      (node (ref "D40") (pin "A") (pinfunction "A_A") (pintype "passive"))
      (node (ref "D47") (pin "C") (pinfunction "C_C") (pintype "passive"))
      (node (ref "D58") (pin "C") (pinfunction "C_C") (pintype "passive"))
      (node (ref "D69") (pin "C") (pinfunction "C_C") (pintype "passive"))
      (node (ref "Q4") (pin "2") (pinfunction "B_2") (pintype "passive"))
      (node (ref "R20") (pin "1") (pinfunction "1_1") (pintype "passive"))
    )
    (net (code "48") (name "Net-(U$2J-1)") (class "Default")
      (node (ref "D18") (pin "A") (pinfunction "A_A") (pintype "passive"))
      (node (ref "D20") (pin "A") (pinfunction "A_A") (pintype "passive"))
      (node (ref "U$2") (pin "L2") (pinfunction "1_L2") (pintype "bidirectional"))
    )
    (net (code "49") (name "Net-(U$2K-1)") (class "Default")
      (node (ref "D7") (pin "A") (pinfunction "A_A") (pintype "passive"))
      (node (ref "D9") (pin "A") (pinfunction "A_A") (pintype "passive"))
      (node (ref "U$2") (pin "M2") (pinfunction "1_M2") (pintype "bidirectional"))
    )
    (net (code "50") (name "Net-(U$2M-1)") (class "Default")
      (node (ref "D49") (pin "A") (pinfunction "A_A") (pintype "passive"))
      (node (ref "D51") (pin "A") (pinfunction "A_A") (pintype "passive"))
      (node (ref "U$2") (pin "P2") (pinfunction "1_P2") (pintype "bidirectional"))
    )
    (net (code "51") (name "Net-(U$2N-1)") (class "Default")
      (node (ref "D31") (pin "C") (pinfunction "C_C") (pintype "passive"))
      (node (ref "D34") (pin "C") (pinfunction "C_C") (pintype "passive"))
      (node (ref "U$2") (pin "R2") (pinfunction "1_R2") (pintype "bidirectional"))
    )
    (net (code "52") (name "Net-(U$2O-1)") (class "Default")
      (node (ref "D59") (pin "A") (pinfunction "A_A") (pintype "passive"))
      (node (ref "D61") (pin "A") (pinfunction "A_A") (pintype "passive"))
      (node (ref "U$2") (pin "S2") (pinfunction "1_S2") (pintype "bidirectional"))
    )
    (net (code "53") (name "Net-(U$2Q-1)") (class "Default")
      (node (ref "D70") (pin "A") (pinfunction "A_A") (pintype "passive"))
      (node (ref "D73") (pin "A") (pinfunction "A_A") (pintype "passive"))
      (node (ref "U$2") (pin "U2") (pinfunction "1_U2") (pintype "bidirectional"))
    )
    (net (code "54") (name "Net-(U$2R-1)") (class "Default")
      (node (ref "D71") (pin "A") (pinfunction "A_A") (pintype "passive"))
      (node (ref "D72") (pin "A") (pinfunction "A_A") (pintype "passive"))
      (node (ref "U$2") (pin "V2") (pinfunction "1_V2") (pintype "bidirectional"))
    )
  )
)
